# rpi_health.net
KiCad netlist of a schematic drawn in EAGLE
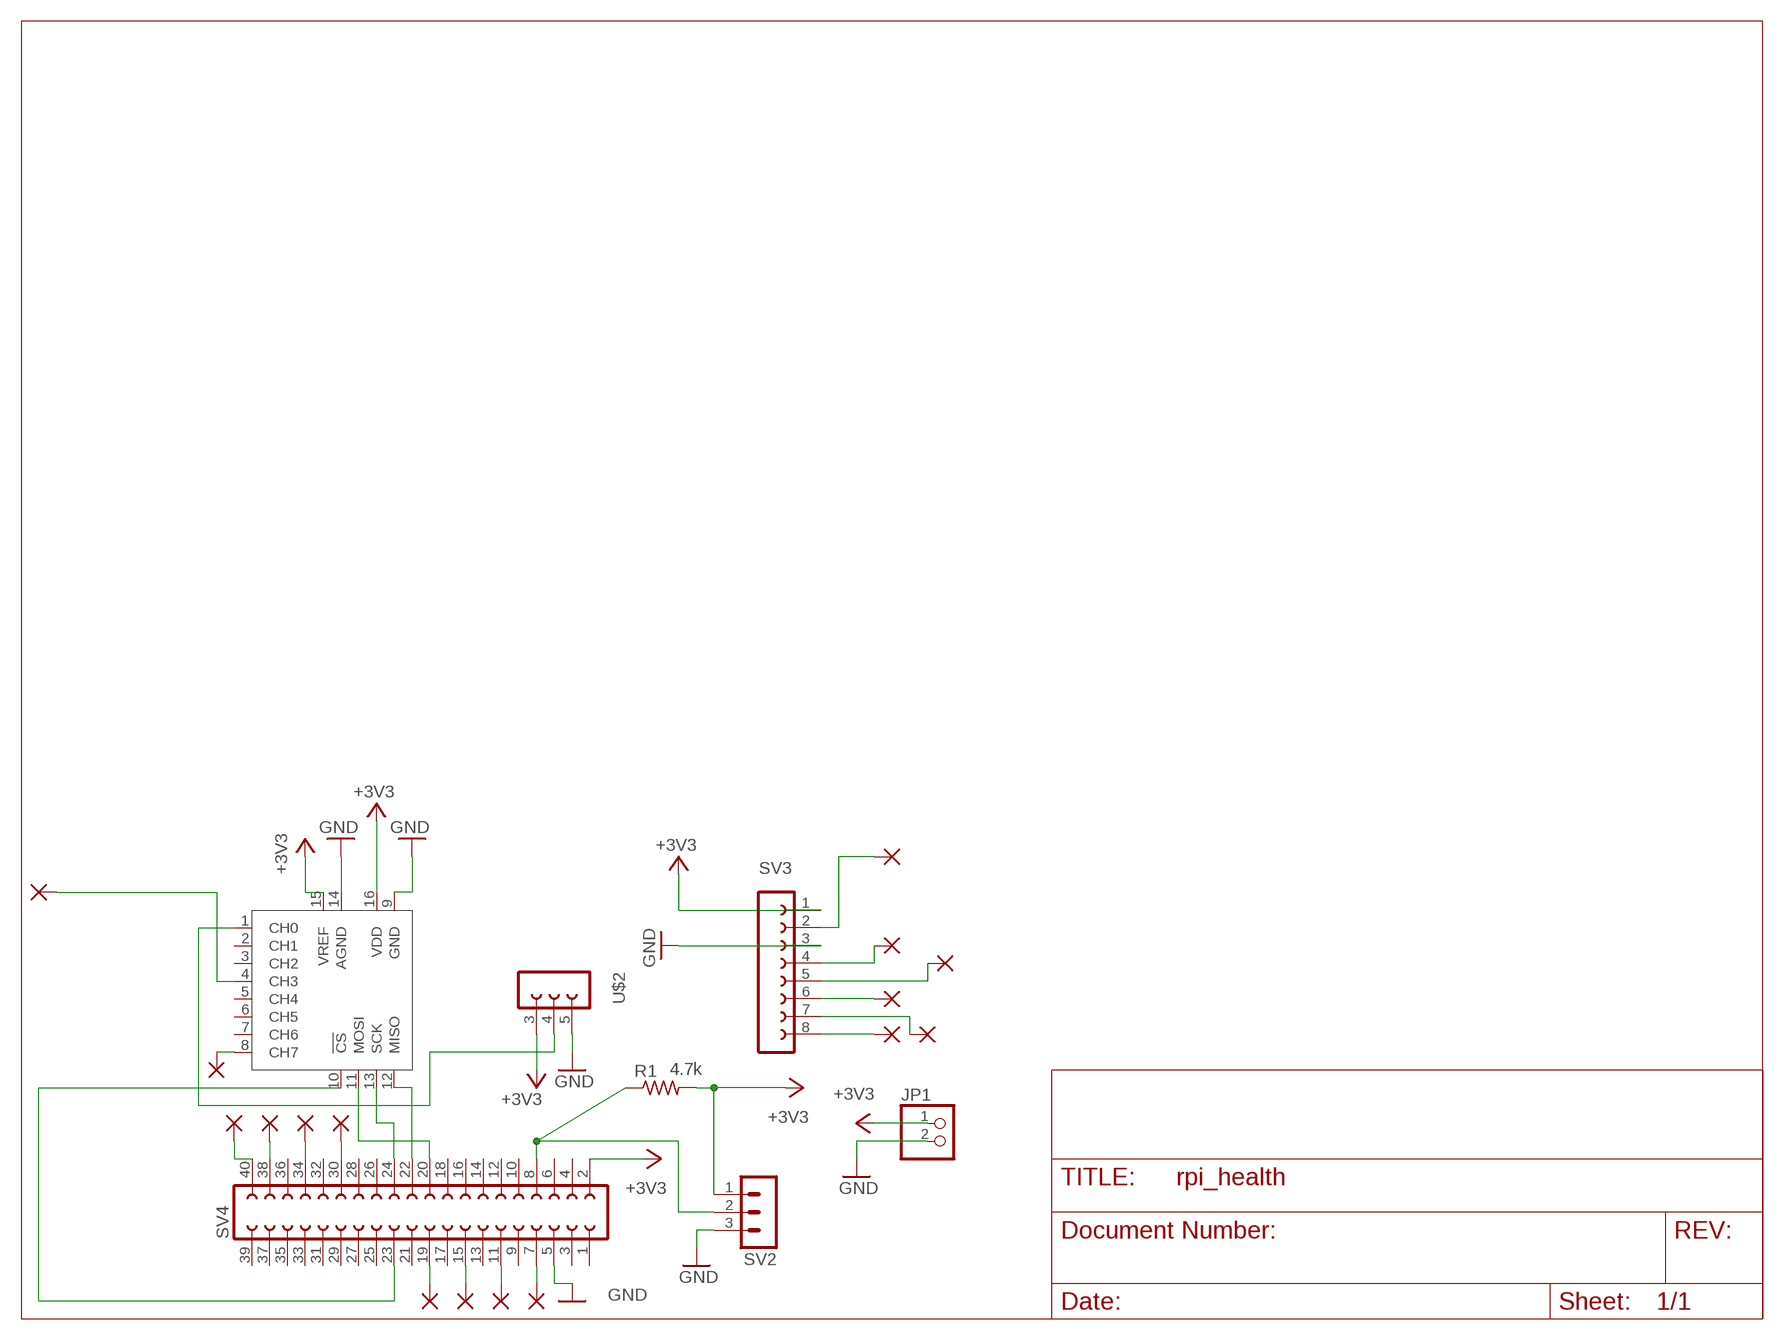
[diagram p0: schematic, sheet 1]

(export (version "E")
  (design (tool "Eeschema 10.0.6"))
  (components
    (comp (ref "JP1")
      (value "PINHD-1X2")
      (footprint "eagle-import:1X02")
      (libsource (lib "eagle-import") (part "PINHD-1X2"))
    )
    (comp (ref "PAD1")
      (value "1,6/0,8")
      (footprint "eagle-import:1,6_0,8")
      (libsource (lib "eagle-import") (part "1,6/0,8"))
    )
    (comp (ref "PAD2")
      (value "1,6/0,8")
      (footprint "eagle-import:1,6_0,8")
      (libsource (lib "eagle-import") (part "1,6/0,8"))
    )
    (comp (ref "PAD3")
      (value "1,6/0,8")
      (footprint "eagle-import:1,6_0,8")
      (libsource (lib "eagle-import") (part "1,6/0,8"))
    )
    (comp (ref "PAD4")
      (value "1,6/0,8")
      (footprint "eagle-import:1,6_0,8")
      (libsource (lib "eagle-import") (part "1,6/0,8"))
    )
    (comp (ref "PAD5")
      (value "1,6/0,8")
      (footprint "eagle-import:1,6_0,8")
      (libsource (lib "eagle-import") (part "1,6/0,8"))
    )
    (comp (ref "PAD6")
      (value "1,6/0,8")
      (footprint "eagle-import:1,6_0,8")
      (libsource (lib "eagle-import") (part "1,6/0,8"))
    )
    (comp (ref "PAD7")
      (value "1,6/0,8")
      (footprint "eagle-import:1,6_0,8")
      (libsource (lib "eagle-import") (part "1,6/0,8"))
    )
    (comp (ref "PAD8")
      (value "1,6/0,8")
      (footprint "eagle-import:1,6_0,8")
      (libsource (lib "eagle-import") (part "1,6/0,8"))
    )
    (comp (ref "PAD9")
      (value "1,6/0,8")
      (footprint "eagle-import:1,6_0,8")
      (libsource (lib "eagle-import") (part "1,6/0,8"))
    )
    (comp (ref "PAD10")
      (value "1,6/0,8")
      (footprint "eagle-import:1,6_0,8")
      (libsource (lib "eagle-import") (part "1,6/0,8"))
    )
    (comp (ref "PAD11")
      (value "1,6/0,8")
      (footprint "eagle-import:1,6_0,8")
      (libsource (lib "eagle-import") (part "1,6/0,8"))
    )
    (comp (ref "PAD12")
      (value "1,6/0,8")
      (footprint "eagle-import:1,6_0,8")
      (libsource (lib "eagle-import") (part "1,6/0,8"))
    )
    (comp (ref "PAD13")
      (value "1,6/0,8")
      (footprint "eagle-import:1,6_0,8")
      (libsource (lib "eagle-import") (part "1,6/0,8"))
    )
    (comp (ref "PAD14")
      (value "1,6/0,8")
      (footprint "eagle-import:1,6_0,8")
      (libsource (lib "eagle-import") (part "1,6/0,8"))
    )
    (comp (ref "PAD15")
      (value "1,6/0,8")
      (footprint "eagle-import:1,6_0,8")
      (libsource (lib "eagle-import") (part "1,6/0,8"))
    )
    (comp (ref "PAD16")
      (value "1,6/0,8")
      (footprint "eagle-import:1,6_0,8")
      (libsource (lib "eagle-import") (part "1,6/0,8"))
    )
    (comp (ref "R1")
      (value "4.7k")
      (footprint "eagle-import:0204_5")
      (libsource (lib "eagle-import") (part "R-US_0204/5"))
    )
    (comp (ref "SV2")
      (value "MA03-1")
      (footprint "eagle-import:MA03-1")
      (libsource (lib "eagle-import") (part "MA03-1"))
    )
    (comp (ref "SV3")
      (value "FE08-1")
      (footprint "eagle-import:FE08")
      (libsource (lib "eagle-import") (part "FE08-1"))
    )
    (comp (ref "SV4")
      (value "FE20-2")
      (footprint "eagle-import:FE20-2")
      (libsource (lib "eagle-import") (part "FE20-2"))
    )
    (comp (ref "U$1")
      (value "MCP3008SL")
      (footprint "eagle-import:SO16")
      (libsource (lib "eagle-import") (part "MCP3008SL"))
    )
    (comp (ref "U$2")
      (value "FE03-1FE03-1")
      (footprint "eagle-import:FE05-1")
      (libsource (lib "eagle-import") (part "FE03-1FE03-1"))
    )
  )
  (nets
    (net (code "1") (name "+3V3") (class "Default")
      (node (ref "JP1") (pin "1") (pinfunction "1_1") (pintype "passive"))
      (node (ref "R1") (pin "2") (pinfunction "2_2") (pintype "passive"))
      (node (ref "SV2") (pin "1") (pinfunction "1_1") (pintype "passive"))
      (node (ref "SV3") (pin "1") (pinfunction "1_1") (pintype "passive"))
      (node (ref "SV4") (pin "2") (pinfunction "2_2") (pintype "passive"))
      (node (ref "U$1") (pin "15") (pinfunction "VREF_15") (pintype "power_in"))
      (node (ref "U$1") (pin "16") (pinfunction "VDD_16") (pintype "power_in"))
      (node (ref "U$2") (pin "3") (pinfunction "3_3") (pintype "passive"))
    )
    (net (code "2") (name "GND") (class "Default")
      (node (ref "JP1") (pin "2") (pinfunction "2_2") (pintype "passive"))
      (node (ref "SV2") (pin "3") (pinfunction "3_3") (pintype "passive"))
      (node (ref "SV3") (pin "3") (pinfunction "3_3") (pintype "passive"))
      (node (ref "SV4") (pin "5") (pinfunction "5_5") (pintype "passive"))
      (node (ref "U$1") (pin "14") (pinfunction "AGND_14") (pintype "power_in"))
      (node (ref "U$1") (pin "9") (pinfunction "GND_9") (pintype "power_in"))
      (node (ref "U$2") (pin "5") (pinfunction "5_5") (pintype "passive"))
    )
    (net (code "3") (name "Net-(PAD1-P)") (class "Default")
      (node (ref "PAD1") (pin "1") (pinfunction "P_1") (pintype "passive"))
      (node (ref "SV3") (pin "4") (pinfunction "4_4") (pintype "passive"))
    )
    (net (code "4") (name "Net-(PAD2-P)") (class "Default")
      (node (ref "PAD2") (pin "1") (pinfunction "P_1") (pintype "passive"))
      (node (ref "SV3") (pin "5") (pinfunction "5_5") (pintype "passive"))
    )
    (net (code "5") (name "Net-(PAD3-P)") (class "Default")
      (node (ref "PAD3") (pin "1") (pinfunction "P_1") (pintype "passive"))
      (node (ref "SV3") (pin "6") (pinfunction "6_6") (pintype "passive"))
    )
    (net (code "6") (name "Net-(PAD4-P)") (class "Default")
      (node (ref "PAD4") (pin "1") (pinfunction "P_1") (pintype "passive"))
      (node (ref "SV4") (pin "7") (pinfunction "7_7") (pintype "passive"))
    )
    (net (code "7") (name "Net-(PAD5-P)") (class "Default")
      (node (ref "PAD5") (pin "1") (pinfunction "P_1") (pintype "passive"))
      (node (ref "SV3") (pin "2") (pinfunction "2_2") (pintype "passive"))
    )
    (net (code "8") (name "Net-(PAD6-P)") (class "Default")
      (node (ref "PAD6") (pin "1") (pinfunction "P_1") (pintype "passive"))
      (node (ref "SV3") (pin "7") (pinfunction "7_7") (pintype "passive"))
    )
    (net (code "9") (name "Net-(PAD7-P)") (class "Default")
      (node (ref "PAD7") (pin "1") (pinfunction "P_1") (pintype "passive"))
      (node (ref "SV3") (pin "8") (pinfunction "8_8") (pintype "passive"))
    )
    (net (code "10") (name "Net-(PAD8-P)") (class "Default")
      (node (ref "PAD8") (pin "1") (pinfunction "P_1") (pintype "passive"))
      (node (ref "SV4") (pin "11") (pinfunction "11_11") (pintype "passive"))
    )
    (net (code "11") (name "Net-(PAD9-P)") (class "Default")
      (node (ref "PAD9") (pin "1") (pinfunction "P_1") (pintype "passive"))
      (node (ref "SV4") (pin "15") (pinfunction "15_15") (pintype "passive"))
    )
    (net (code "12") (name "Net-(PAD10-P)") (class "Default")
      (node (ref "PAD10") (pin "1") (pinfunction "P_1") (pintype "passive"))
      (node (ref "SV4") (pin "19") (pinfunction "19_19") (pintype "passive"))
    )
    (net (code "13") (name "Net-(PAD11-P)") (class "Default")
      (node (ref "PAD11") (pin "1") (pinfunction "P_1") (pintype "passive"))
      (node (ref "SV4") (pin "30") (pinfunction "30_30") (pintype "passive"))
    )
    (net (code "14") (name "Net-(PAD12-P)") (class "Default")
      (node (ref "PAD12") (pin "1") (pinfunction "P_1") (pintype "passive"))
      (node (ref "SV4") (pin "34") (pinfunction "34_34") (pintype "passive"))
    )
    (net (code "15") (name "Net-(PAD13-P)") (class "Default")
      (node (ref "PAD13") (pin "1") (pinfunction "P_1") (pintype "passive"))
      (node (ref "SV4") (pin "38") (pinfunction "38_38") (pintype "passive"))
    )
    (net (code "16") (name "Net-(PAD14-P)") (class "Default")
      (node (ref "PAD14") (pin "1") (pinfunction "P_1") (pintype "passive"))
      (node (ref "SV4") (pin "40") (pinfunction "40_40") (pintype "passive"))
    )
    (net (code "17") (name "Net-(PAD15-P)") (class "Default")
      (node (ref "PAD15") (pin "1") (pinfunction "P_1") (pintype "passive"))
      (node (ref "U$1") (pin "4") (pinfunction "CH3_4") (pintype "input"))
    )
    (net (code "18") (name "Net-(PAD16-P)") (class "Default")
      (node (ref "PAD16") (pin "1") (pinfunction "P_1") (pintype "passive"))
      (node (ref "U$1") (pin "8") (pinfunction "CH7_8") (pintype "input"))
    )
    (net (code "19") (name "Net-(R1-Pad1)") (class "Default")
      (node (ref "R1") (pin "1") (pinfunction "1_1") (pintype "passive"))
      (node (ref "SV2") (pin "2") (pinfunction "2_2") (pintype "passive"))
      (node (ref "SV4") (pin "8") (pinfunction "8_8") (pintype "passive"))
    )
    (net (code "20") (name "Net-(U$1-CH0)") (class "Default")
      (node (ref "U$1") (pin "1") (pinfunction "CH0_1") (pintype "input"))
      (node (ref "U$2") (pin "4") (pinfunction "4_4") (pintype "passive"))
    )
    (net (code "21") (name "Net-(U$1-MISO)") (class "Default")
      (node (ref "SV4") (pin "22") (pinfunction "22_22") (pintype "passive"))
      (node (ref "U$1") (pin "12") (pinfunction "MISO_12") (pintype "output"))
    )
    (net (code "22") (name "Net-(U$1-MOSI)") (class "Default")
      (node (ref "SV4") (pin "20") (pinfunction "20_20") (pintype "passive"))
      (node (ref "U$1") (pin "11") (pinfunction "MOSI_11") (pintype "input"))
    )
    (net (code "23") (name "Net-(U$1-SCK)") (class "Default")
      (node (ref "SV4") (pin "24") (pinfunction "24_24") (pintype "passive"))
      (node (ref "U$1") (pin "13") (pinfunction "SCK_13") (pintype "input"))
    )
    (net (code "24") (name "Net-(U$1-~{CS})") (class "Default")
      (node (ref "SV4") (pin "23") (pinfunction "23_23") (pintype "passive"))
      (node (ref "U$1") (pin "10") (pinfunction "~{CS}_10") (pintype "input"))
    )
    (net (code "25") (name "unconnected-(SV4-Pad1)") (class "Default")
      (node (ref "SV4") (pin "1") (pinfunction "1_1") (pintype "passive"))
    )
    (net (code "26") (name "unconnected-(SV4-Pad3)") (class "Default")
      (node (ref "SV4") (pin "3") (pinfunction "3_3") (pintype "passive"))
    )
    (net (code "27") (name "unconnected-(SV4-Pad4)") (class "Default")
      (node (ref "SV4") (pin "4") (pinfunction "4_4") (pintype "passive"))
    )
    (net (code "28") (name "unconnected-(SV4-Pad6)") (class "Default")
      (node (ref "SV4") (pin "6") (pinfunction "6_6") (pintype "passive"))
    )
    (net (code "29") (name "unconnected-(SV4-Pad9)") (class "Default")
      (node (ref "SV4") (pin "9") (pinfunction "9_9") (pintype "passive"))
    )
    (net (code "30") (name "unconnected-(SV4-Pad10)") (class "Default")
      (node (ref "SV4") (pin "10") (pinfunction "10_10") (pintype "passive"))
    )
    (net (code "31") (name "unconnected-(SV4-Pad12)") (class "Default")
      (node (ref "SV4") (pin "12") (pinfunction "12_12") (pintype "passive"))
    )
    (net (code "32") (name "unconnected-(SV4-Pad13)") (class "Default")
      (node (ref "SV4") (pin "13") (pinfunction "13_13") (pintype "passive"))
    )
    (net (code "33") (name "unconnected-(SV4-Pad14)") (class "Default")
      (node (ref "SV4") (pin "14") (pinfunction "14_14") (pintype "passive"))
    )
    (net (code "34") (name "unconnected-(SV4-Pad16)") (class "Default")
      (node (ref "SV4") (pin "16") (pinfunction "16_16") (pintype "passive"))
    )
    (net (code "35") (name "unconnected-(SV4-Pad17)") (class "Default")
      (node (ref "SV4") (pin "17") (pinfunction "17_17") (pintype "passive"))
    )
    (net (code "36") (name "unconnected-(SV4-Pad18)") (class "Default")
      (node (ref "SV4") (pin "18") (pinfunction "18_18") (pintype "passive"))
    )
    (net (code "37") (name "unconnected-(SV4-Pad21)") (class "Default")
      (node (ref "SV4") (pin "21") (pinfunction "21_21") (pintype "passive"))
    )
    (net (code "38") (name "unconnected-(SV4-Pad25)") (class "Default")
      (node (ref "SV4") (pin "25") (pinfunction "25_25") (pintype "passive"))
    )
    (net (code "39") (name "unconnected-(SV4-Pad26)") (class "Default")
      (node (ref "SV4") (pin "26") (pinfunction "26_26") (pintype "passive"))
    )
    (net (code "40") (name "unconnected-(SV4-Pad27)") (class "Default")
      (node (ref "SV4") (pin "27") (pinfunction "27_27") (pintype "passive"))
    )
    (net (code "41") (name "unconnected-(SV4-Pad28)") (class "Default")
      (node (ref "SV4") (pin "28") (pinfunction "28_28") (pintype "passive"))
    )
    (net (code "42") (name "unconnected-(SV4-Pad29)") (class "Default")
      (node (ref "SV4") (pin "29") (pinfunction "29_29") (pintype "passive"))
    )
    (net (code "43") (name "unconnected-(SV4-Pad31)") (class "Default")
      (node (ref "SV4") (pin "31") (pinfunction "31_31") (pintype "passive"))
    )
    (net (code "44") (name "unconnected-(SV4-Pad32)") (class "Default")
      (node (ref "SV4") (pin "32") (pinfunction "32_32") (pintype "passive"))
    )
    (net (code "45") (name "unconnected-(SV4-Pad33)") (class "Default")
      (node (ref "SV4") (pin "33") (pinfunction "33_33") (pintype "passive"))
    )
    (net (code "46") (name "unconnected-(SV4-Pad35)") (class "Default")
      (node (ref "SV4") (pin "35") (pinfunction "35_35") (pintype "passive"))
    )
    (net (code "47") (name "unconnected-(SV4-Pad36)") (class "Default")
      (node (ref "SV4") (pin "36") (pinfunction "36_36") (pintype "passive"))
    )
    (net (code "48") (name "unconnected-(SV4-Pad37)") (class "Default")
      (node (ref "SV4") (pin "37") (pinfunction "37_37") (pintype "passive"))
    )
    (net (code "49") (name "unconnected-(SV4-Pad39)") (class "Default")
      (node (ref "SV4") (pin "39") (pinfunction "39_39") (pintype "passive"))
    )
    (net (code "50") (name "unconnected-(U$1-CH1-Pad2)") (class "Default")
      (node (ref "U$1") (pin "2") (pinfunction "CH1_2") (pintype "input"))
    )
    (net (code "51") (name "unconnected-(U$1-CH2-Pad3)") (class "Default")
      (node (ref "U$1") (pin "3") (pinfunction "CH2_3") (pintype "input"))
    )
    (net (code "52") (name "unconnected-(U$1-CH4-Pad5)") (class "Default")
      (node (ref "U$1") (pin "5") (pinfunction "CH4_5") (pintype "input"))
    )
    (net (code "53") (name "unconnected-(U$1-CH5-Pad6)") (class "Default")
      (node (ref "U$1") (pin "6") (pinfunction "CH5_6") (pintype "input"))
    )
    (net (code "54") (name "unconnected-(U$1-CH6-Pad7)") (class "Default")
      (node (ref "U$1") (pin "7") (pinfunction "CH6_7") (pintype "input"))
    )
  )
)
